# microSD.net
KiCad netlist of a schematic drawn in Altium Designer
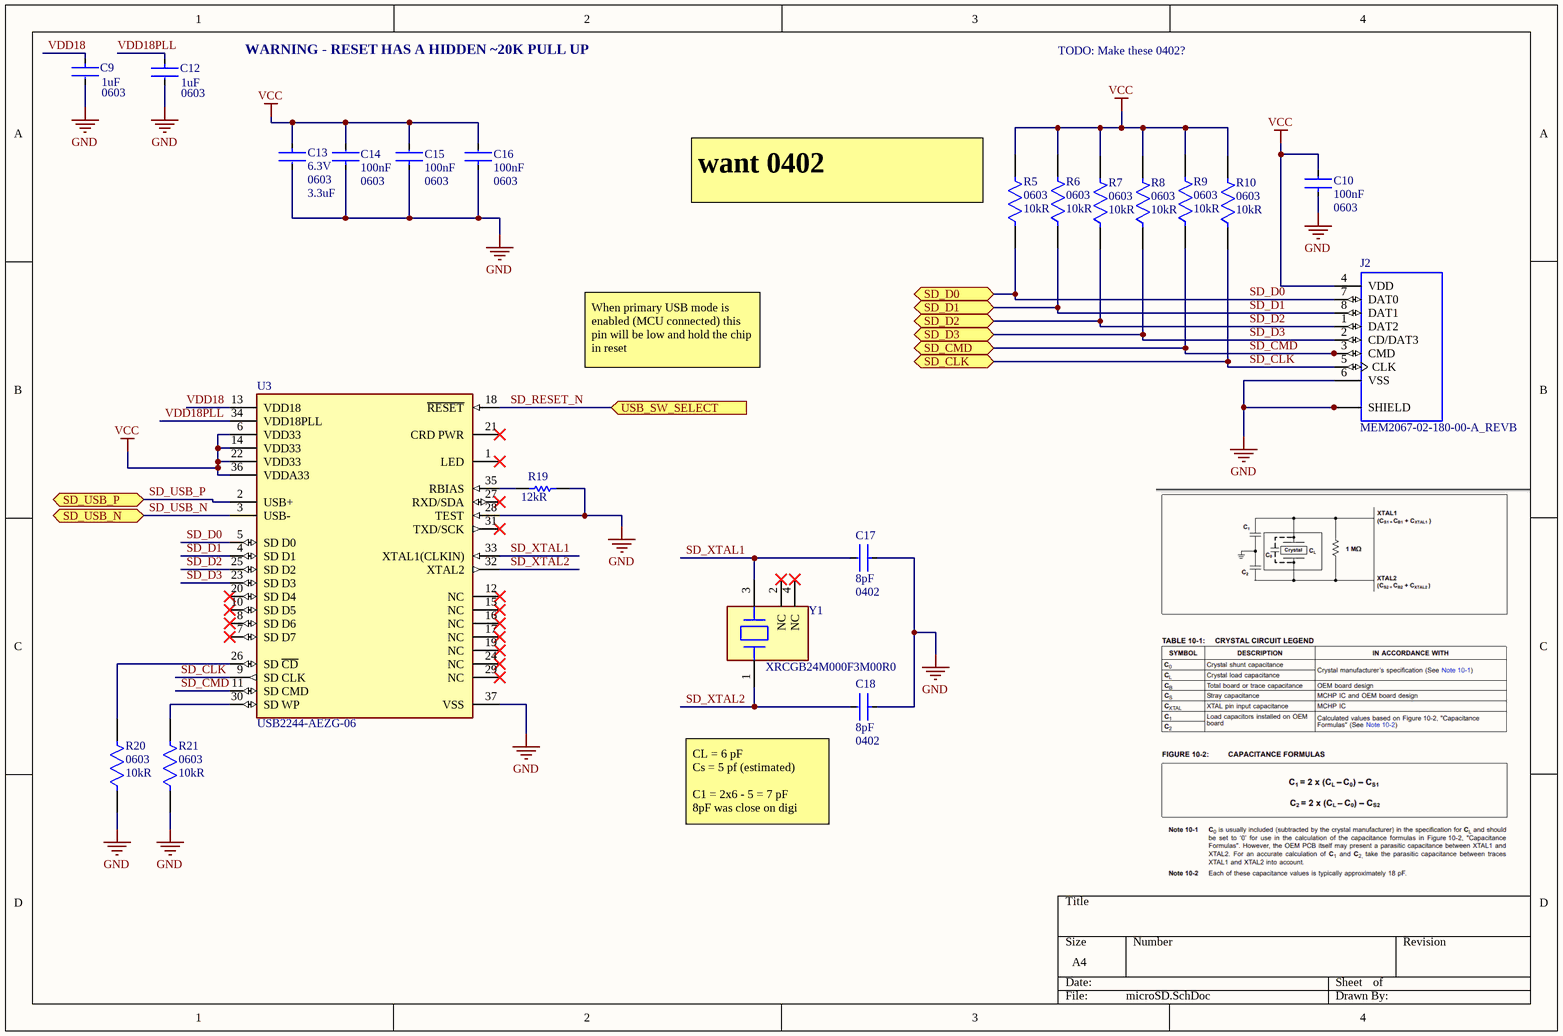
[diagram p0: microSD.SchDoc]

(export (version "E")
  (design (tool "Eeschema 10.0.6"))
  (components
    (comp (ref "C9")
      (value "UMK107BJ105KA-T")
      (footprint "FP-0603-L_1_6_0_1-W_0_8_0-IPC_A")
      (description "None")
      (fields
        (field (name "TOLERANCE") "10%")
        (field (name "CASE/PACKAGE") "0603")
        (field (name "CAPACITANCE") "1uF")
      )
      (libsource (lib "Altium Content Vault") (part "02cd4be3c70576c341d710602a673aa"))
    )
    (comp (ref "C10")
      (value "CL10B104KB8WPNC")
      (footprint "FP-CL10-IPC_A")
      (description "Cap Ceramic 100nF 50V X7R ±10% Pad SMD 0603 +125°C T/R")
      (fields
        (field (name "CAPACITANCE") "100nF")
        (field (name "CASE/PACKAGE") "0603")
        (field (name "TOLERANCE") "10%")
      )
      (libsource (lib "Altium Content Vault") (part "b4654b650e69147ec39a6b967a45e02"))
    )
    (comp (ref "C12")
      (value "UMK107BJ105KA-T")
      (footprint "FP-0603-L_1_6_0_1-W_0_8_0-IPC_A")
      (description "None")
      (fields
        (field (name "TOLERANCE") "10%")
        (field (name "CASE/PACKAGE") "0603")
        (field (name "CAPACITANCE") "1uF")
      )
      (libsource (lib "Altium Content Vault") (part "02cd4be3c70576c341d710602a673aa"))
    )
    (comp (ref "C13")
      (value "C1608X7S0J335K080AC")
      (footprint "FP-C1608-080-0_1-MFG")
      (description "Multilayer Ceramic Capacitors 3.3μF ±10% 6.3V X7S SMD 0603")
      (fields
        (field (name "VOLTAGE RATING") "6.3V")
        (field (name "CASE CODE (IMPERIAL)") "0603")
        (field (name "CAPACITANCE") "3.3uF")
        (field (name "TOLERANCE") "10%")
      )
      (libsource (lib "Altium Content Vault") (part "236180d848d6139a670b325ea6854c9"))
    )
    (comp (ref "C14")
      (value "CL10B104KB8WPNC")
      (footprint "FP-CL10-IPC_A")
      (description "Cap Ceramic 100nF 50V X7R ±10% Pad SMD 0603 +125°C T/R")
      (fields
        (field (name "CAPACITANCE") "100nF")
        (field (name "CASE/PACKAGE") "0603")
        (field (name "TOLERANCE") "10%")
      )
      (libsource (lib "Altium Content Vault") (part "b4654b650e69147ec39a6b967a45e02"))
    )
    (comp (ref "C15")
      (value "CL10B104KB8WPNC")
      (footprint "FP-CL10-IPC_A")
      (description "Cap Ceramic 100nF 50V X7R ±10% Pad SMD 0603 +125°C T/R")
      (fields
        (field (name "CAPACITANCE") "100nF")
        (field (name "CASE/PACKAGE") "0603")
        (field (name "TOLERANCE") "10%")
      )
      (libsource (lib "Altium Content Vault") (part "b4654b650e69147ec39a6b967a45e02"))
    )
    (comp (ref "C16")
      (value "CL10B104KB8WPNC")
      (footprint "FP-CL10-IPC_A")
      (description "Cap Ceramic 100nF 50V X7R ±10% Pad SMD 0603 +125°C T/R")
      (fields
        (field (name "CAPACITANCE") "100nF")
        (field (name "CASE/PACKAGE") "0603")
        (field (name "TOLERANCE") "10%")
      )
      (libsource (lib "Altium Content Vault") (part "b4654b650e69147ec39a6b967a45e02"))
    )
    (comp (ref "C17")
      (value "CL05C080DB51PNC")
      (footprint "FP-CL522-IPC_C")
      (description "Cap Ceramic 8pF 50V C0G ±0.5pF SMD 0402 +125°C Paper T/R")
      (fields (field (name "CAPACITANCE") "8pF") (field (name "PACKAGE") "0402"))
      (libsource (lib "Altium Content Vault") (part "b4654b650e69147ec39a6b967a45e02"))
    )
    (comp (ref "C18")
      (value "CL05C080DB51PNC")
      (footprint "FP-CL522-IPC_C")
      (description "Cap Ceramic 8pF 50V C0G ±0.5pF SMD 0402 +125°C Paper T/R")
      (fields (field (name "CAPACITANCE") "8pF") (field (name "PACKAGE") "0402"))
      (libsource (lib "Altium Content Vault") (part "b4654b650e69147ec39a6b967a45e02"))
    )
    (comp (ref "J2")
      (value "MEM2067-02-180-00-A_REVB")
      (footprint "WiCAN_lib:GCT_MEM2067-02-180-00-A_REVB")
      (description "Micro SD Memory Card ConnectorSMT, Hinged, 1.80mm Profile")
      (libsource (lib "WiCAN_lib") (part "MEM2067-02-180-00-A_REVB"))
    )
    (comp (ref "R5")
      (value "RMCF0603JG10K0")
      (footprint "FP-RMCF0603-MFG")
      (description "10kΩ ±5% 0.1W 0603 Thick Film Chip Resistor AEC-Q200 compliant")
      (fields
        (field (name "TOLERANCE") "5%")
        (field (name "CASE CODE (IMPERIAL)") "0603")
        (field (name "RESISTANCE") "10kR")
      )
      (libsource (lib "Altium Content Vault") (part "1029c3af85768c4190bb7ad29bc67b5"))
    )
    (comp (ref "R6")
      (value "RMCF0603JG10K0")
      (footprint "FP-RMCF0603-MFG")
      (description "10kΩ ±5% 0.1W 0603 Thick Film Chip Resistor AEC-Q200 compliant")
      (fields
        (field (name "TOLERANCE") "5%")
        (field (name "CASE CODE (IMPERIAL)") "0603")
        (field (name "RESISTANCE") "10kR")
      )
      (libsource (lib "Altium Content Vault") (part "1029c3af85768c4190bb7ad29bc67b5"))
    )
    (comp (ref "R7")
      (value "RMCF0603JG10K0")
      (footprint "FP-RMCF0603-MFG")
      (description "10kΩ ±5% 0.1W 0603 Thick Film Chip Resistor AEC-Q200 compliant")
      (fields
        (field (name "TOLERANCE") "5%")
        (field (name "CASE CODE (IMPERIAL)") "0603")
        (field (name "RESISTANCE") "10kR")
      )
      (libsource (lib "Altium Content Vault") (part "1029c3af85768c4190bb7ad29bc67b5"))
    )
    (comp (ref "R8")
      (value "RMCF0603JG10K0")
      (footprint "FP-RMCF0603-MFG")
      (description "10kΩ ±5% 0.1W 0603 Thick Film Chip Resistor AEC-Q200 compliant")
      (fields
        (field (name "TOLERANCE") "5%")
        (field (name "CASE CODE (IMPERIAL)") "0603")
        (field (name "RESISTANCE") "10kR")
      )
      (libsource (lib "Altium Content Vault") (part "1029c3af85768c4190bb7ad29bc67b5"))
    )
    (comp (ref "R9")
      (value "RMCF0603JG10K0")
      (footprint "FP-RMCF0603-MFG")
      (description "10kΩ ±5% 0.1W 0603 Thick Film Chip Resistor AEC-Q200 compliant")
      (fields
        (field (name "TOLERANCE") "5%")
        (field (name "CASE CODE (IMPERIAL)") "0603")
        (field (name "RESISTANCE") "10kR")
      )
      (libsource (lib "Altium Content Vault") (part "1029c3af85768c4190bb7ad29bc67b5"))
    )
    (comp (ref "R10")
      (value "RMCF0603JG10K0")
      (footprint "FP-RMCF0603-MFG")
      (description "10kΩ ±5% 0.1W 0603 Thick Film Chip Resistor AEC-Q200 compliant")
      (fields
        (field (name "TOLERANCE") "5%")
        (field (name "CASE CODE (IMPERIAL)") "0603")
        (field (name "RESISTANCE") "10kR")
      )
      (libsource (lib "Altium Content Vault") (part "1029c3af85768c4190bb7ad29bc67b5"))
    )
    (comp (ref "R19")
      (value "RC0603FR-1312KL")
      (footprint "RESC1608X55X25LL10T15")
      (fields (field (name "MANUFACTURER") "Yageo") (field (name "RESISTANCE") "12kR"))
      (libsource (lib "Altium Content Vault") (part "RES"))
    )
    (comp (ref "R20")
      (value "RMCF0603JG10K0")
      (footprint "FP-RMCF0603-MFG")
      (description "10kΩ ±5% 0.1W 0603 Thick Film Chip Resistor AEC-Q200 compliant")
      (fields
        (field (name "TOLERANCE") "5%")
        (field (name "CASE CODE (IMPERIAL)") "0603")
        (field (name "RESISTANCE") "10kR")
      )
      (libsource (lib "Altium Content Vault") (part "1029c3af85768c4190bb7ad29bc67b5"))
    )
    (comp (ref "R21")
      (value "RMCF0603JG10K0")
      (footprint "FP-RMCF0603-MFG")
      (description "10kΩ ±5% 0.1W 0603 Thick Film Chip Resistor AEC-Q200 compliant")
      (fields
        (field (name "TOLERANCE") "5%")
        (field (name "CASE CODE (IMPERIAL)") "0603")
        (field (name "RESISTANCE") "10kR")
      )
      (libsource (lib "Altium Content Vault") (part "1029c3af85768c4190bb7ad29bc67b5"))
    )
    (comp (ref "U3")
      (value "USB2244-AEZG-06")
      (footprint "FP-36QFN-4106-6x6B-MFG")
      (description "IC MEDIA CTRLR USB 2.0 36-QFNE3")
      (libsource (lib "Altium Content Vault") (part "52cbab052c9bdc7a267728846530958"))
    )
    (comp (ref "Y1")
      (value "XRCGB24M000F3M00R0")
      (footprint "FP-XRCGB_F_N-MFG")
      (description "CRYSTAL 24.0000MHZ 6PF SMD")
      (fields (field (name "TOLERANCE") "30ppm"))
      (libsource (lib "Altium Content Vault") (part "13d16a3a70fb0809ccfd81e284aeb9d"))
    )
  )
  (nets
    (net (code "1") (name "/SD_CLK") (class "Default")
      (node (ref "J2") (pin "5") (pinfunction "CLK_5") (pintype "bidirectional"))
      (node (ref "R10") (pin "1") (pinfunction "1_1") (pintype "passive"))
      (node (ref "U3") (pin "9") (pinfunction "SD_CLK_9") (pintype "output"))
    )
    (net (code "2") (name "/SD_CMD") (class "Default")
      (node (ref "J2") (pin "3") (pinfunction "CMD_3") (pintype "bidirectional"))
      (node (ref "R9") (pin "1") (pinfunction "1_1") (pintype "passive"))
      (node (ref "U3") (pin "11") (pinfunction "SD_CMD_11") (pintype "bidirectional"))
    )
    (net (code "3") (name "/SD_D0") (class "Default")
      (node (ref "J2") (pin "7") (pinfunction "DAT0_7") (pintype "bidirectional"))
      (node (ref "R5") (pin "1") (pinfunction "1_1") (pintype "passive"))
      (node (ref "U3") (pin "5") (pinfunction "SD_D0_5") (pintype "bidirectional"))
    )
    (net (code "4") (name "/SD_D1") (class "Default")
      (node (ref "J2") (pin "8") (pinfunction "DAT1_8") (pintype "bidirectional"))
      (node (ref "R6") (pin "1") (pinfunction "1_1") (pintype "passive"))
      (node (ref "U3") (pin "4") (pinfunction "SD_D1_4") (pintype "bidirectional"))
    )
    (net (code "5") (name "/SD_D2") (class "Default")
      (node (ref "J2") (pin "1") (pinfunction "DAT2_1") (pintype "bidirectional"))
      (node (ref "R7") (pin "1") (pinfunction "1_1") (pintype "passive"))
      (node (ref "U3") (pin "25") (pinfunction "SD_D2_25") (pintype "bidirectional"))
    )
    (net (code "6") (name "/SD_D3") (class "Default")
      (node (ref "J2") (pin "2") (pinfunction "CD/DAT3_2") (pintype "bidirectional"))
      (node (ref "R8") (pin "1") (pinfunction "1_1") (pintype "passive"))
      (node (ref "U3") (pin "23") (pinfunction "SD_D3_23") (pintype "bidirectional"))
    )
    (net (code "7") (name "/SD_RESET_N") (class "Default")
      (node (ref "U3") (pin "18") (pinfunction "~{RESET}_18") (pintype "input"))
    )
    (net (code "8") (name "/SD_USB_N") (class "Default")
      (node (ref "U3") (pin "3") (pinfunction "USB-_3") (pintype "passive"))
    )
    (net (code "9") (name "/SD_USB_P") (class "Default")
      (node (ref "U3") (pin "2") (pinfunction "USB+_2") (pintype "passive"))
    )
    (net (code "10") (name "/SD_XTAL1") (class "Default")
      (node (ref "C17") (pin "2") (pinfunction "2_2") (pintype "passive"))
      (node (ref "U3") (pin "33") (pinfunction "XTAL1(CLKIN)_33") (pintype "input"))
      (node (ref "Y1") (pin "3") (pinfunction "2_Input/Output_3") (pintype "passive"))
    )
    (net (code "11") (name "/SD_XTAL2") (class "Default")
      (node (ref "C18") (pin "2") (pinfunction "2_2") (pintype "passive"))
      (node (ref "U3") (pin "32") (pinfunction "XTAL2_32") (pintype "output"))
      (node (ref "Y1") (pin "1") (pinfunction "1_Input/Output_1") (pintype "passive"))
    )
    (net (code "12") (name "/VDD18") (class "Default")
      (node (ref "C9") (pin "1") (pinfunction "1_1") (pintype "passive"))
      (node (ref "U3") (pin "13") (pinfunction "VDD18_13") (pintype "power_in"))
    )
    (net (code "13") (name "/VDD18PLL") (class "Default")
      (node (ref "C12") (pin "1") (pinfunction "1_1") (pintype "passive"))
      (node (ref "U3") (pin "34") (pinfunction "VDD18PLL_34") (pintype "power_in"))
    )
    (net (code "14") (name "GND") (class "Default")
      (node (ref "C10") (pin "1") (pinfunction "1_1") (pintype "passive"))
      (node (ref "C12") (pin "2") (pinfunction "2_2") (pintype "passive"))
      (node (ref "C13") (pin "1") (pinfunction "1_1") (pintype "passive"))
      (node (ref "C14") (pin "1") (pinfunction "1_1") (pintype "passive"))
      (node (ref "C15") (pin "1") (pinfunction "1_1") (pintype "passive"))
      (node (ref "C16") (pin "1") (pinfunction "1_1") (pintype "passive"))
      (node (ref "C17") (pin "1") (pinfunction "1_1") (pintype "passive"))
      (node (ref "C18") (pin "1") (pinfunction "1_1") (pintype "passive"))
      (node (ref "C9") (pin "2") (pinfunction "2_2") (pintype "passive"))
      (node (ref "J2") (pin "10") (pinfunction "SHIELD_10") (pintype "passive"))
      (node (ref "J2") (pin "11") (pinfunction "SHIELD_11") (pintype "passive"))
      (node (ref "J2") (pin "12") (pinfunction "SHIELD_12") (pintype "passive"))
      (node (ref "J2") (pin "6") (pinfunction "VSS_6") (pintype "power_in"))
      (node (ref "J2") (pin "9") (pinfunction "SHIELD_9") (pintype "passive"))
      (node (ref "R19") (pin "2") (pinfunction "2_2") (pintype "passive"))
      (node (ref "R20") (pin "1") (pinfunction "1_1") (pintype "passive"))
      (node (ref "R21") (pin "1") (pinfunction "1_1") (pintype "passive"))
      (node (ref "U3") (pin "28") (pinfunction "TEST_28") (pintype "input"))
      (node (ref "U3") (pin "37") (pinfunction "VSS_37") (pintype "power_in"))
    )
    (net (code "15") (name "Net-(U3-RBIAS)") (class "Default")
      (node (ref "R19") (pin "1") (pinfunction "1_1") (pintype "passive"))
      (node (ref "U3") (pin "35") (pinfunction "RBIAS_35") (pintype "input"))
    )
    (net (code "16") (name "Net-(U3-SD_WP)") (class "Default")
      (node (ref "R21") (pin "2") (pinfunction "2_2") (pintype "passive"))
      (node (ref "U3") (pin "30") (pinfunction "SD_WP_30") (pintype "bidirectional"))
    )
    (net (code "17") (name "Net-(U3-SD_~{CD})") (class "Default")
      (node (ref "R20") (pin "2") (pinfunction "2_2") (pintype "passive"))
      (node (ref "U3") (pin "26") (pinfunction "SD_~{CD}_26") (pintype "bidirectional"))
    )
    (net (code "18") (name "VCC") (class "Default")
      (node (ref "C10") (pin "2") (pinfunction "2_2") (pintype "passive"))
      (node (ref "C13") (pin "2") (pinfunction "2_2") (pintype "passive"))
      (node (ref "C14") (pin "2") (pinfunction "2_2") (pintype "passive"))
      (node (ref "C15") (pin "2") (pinfunction "2_2") (pintype "passive"))
      (node (ref "C16") (pin "2") (pinfunction "2_2") (pintype "passive"))
      (node (ref "J2") (pin "4") (pinfunction "VDD_4") (pintype "passive"))
      (node (ref "R10") (pin "2") (pinfunction "2_2") (pintype "passive"))
      (node (ref "R5") (pin "2") (pinfunction "2_2") (pintype "passive"))
      (node (ref "R6") (pin "2") (pinfunction "2_2") (pintype "passive"))
      (node (ref "R7") (pin "2") (pinfunction "2_2") (pintype "passive"))
      (node (ref "R8") (pin "2") (pinfunction "2_2") (pintype "passive"))
      (node (ref "R9") (pin "2") (pinfunction "2_2") (pintype "passive"))
      (node (ref "U3") (pin "14") (pinfunction "VDD33_14") (pintype "power_in"))
      (node (ref "U3") (pin "22") (pinfunction "VDD33_22") (pintype "power_in"))
      (node (ref "U3") (pin "36") (pinfunction "VDDA33_36") (pintype "power_in"))
      (node (ref "U3") (pin "6") (pinfunction "VDD33_6") (pintype "power_in"))
    )
    (net (code "19") (name "unconnected-(U3-CRD_PWR-Pad21)") (class "Default")
      (node (ref "U3") (pin "21") (pinfunction "CRD_PWR_21") (pintype "power_in+no_connect"))
    )
    (net (code "20") (name "unconnected-(U3-LED-Pad1)") (class "Default")
      (node (ref "U3") (pin "1") (pinfunction "LED_1") (pintype "passive+no_connect"))
    )
    (net (code "21") (name "unconnected-(U3-NC-Pad12)") (class "Default")
      (node (ref "U3") (pin "12") (pinfunction "NC_12") (pintype "passive+no_connect"))
    )
    (net (code "22") (name "unconnected-(U3-NC-Pad15)") (class "Default")
      (node (ref "U3") (pin "15") (pinfunction "NC_15") (pintype "passive+no_connect"))
    )
    (net (code "23") (name "unconnected-(U3-NC-Pad16)") (class "Default")
      (node (ref "U3") (pin "16") (pinfunction "NC_16") (pintype "passive+no_connect"))
    )
    (net (code "24") (name "unconnected-(U3-NC-Pad17)") (class "Default")
      (node (ref "U3") (pin "17") (pinfunction "NC_17") (pintype "passive+no_connect"))
    )
    (net (code "25") (name "unconnected-(U3-NC-Pad19)") (class "Default")
      (node (ref "U3") (pin "19") (pinfunction "NC_19") (pintype "passive+no_connect"))
    )
    (net (code "26") (name "unconnected-(U3-NC-Pad24)") (class "Default")
      (node (ref "U3") (pin "24") (pinfunction "NC_24") (pintype "passive+no_connect"))
    )
    (net (code "27") (name "unconnected-(U3-NC-Pad29)") (class "Default")
      (node (ref "U3") (pin "29") (pinfunction "NC_29") (pintype "passive+no_connect"))
    )
    (net (code "28") (name "unconnected-(U3-RXD{slash}SDA-Pad27)") (class "Default")
      (node (ref "U3") (pin "27") (pinfunction "RXD/SDA_27") (pintype "bidirectional+no_connect"))
    )
    (net (code "29") (name "unconnected-(U3-SD_D4-Pad20)") (class "Default")
      (node (ref "U3") (pin "20") (pinfunction "SD_D4_20") (pintype "bidirectional+no_connect"))
    )
    (net (code "30") (name "unconnected-(U3-SD_D5-Pad10)") (class "Default")
      (node (ref "U3") (pin "10") (pinfunction "SD_D5_10") (pintype "bidirectional+no_connect"))
    )
    (net (code "31") (name "unconnected-(U3-SD_D6-Pad8)") (class "Default")
      (node (ref "U3") (pin "8") (pinfunction "SD_D6_8") (pintype "bidirectional+no_connect"))
    )
    (net (code "32") (name "unconnected-(U3-SD_D7-Pad7)") (class "Default")
      (node (ref "U3") (pin "7") (pinfunction "SD_D7_7") (pintype "bidirectional+no_connect"))
    )
    (net (code "33") (name "unconnected-(U3-TXD{slash}SCK-Pad31)") (class "Default")
      (node (ref "U3") (pin "31") (pinfunction "TXD/SCK_31") (pintype "output+no_connect"))
    )
    (net (code "34") (name "unconnected-(Y1-NC-Pad2)") (class "Default")
      (node (ref "Y1") (pin "2") (pinfunction "NC_2") (pintype "passive+no_connect"))
    )
    (net (code "35") (name "unconnected-(Y1-NC-Pad4)") (class "Default")
      (node (ref "Y1") (pin "4") (pinfunction "NC_4") (pintype "passive+no_connect"))
    )
  )
)
